# FT601.net
KiCad netlist of a schematic drawn in Altium Designer
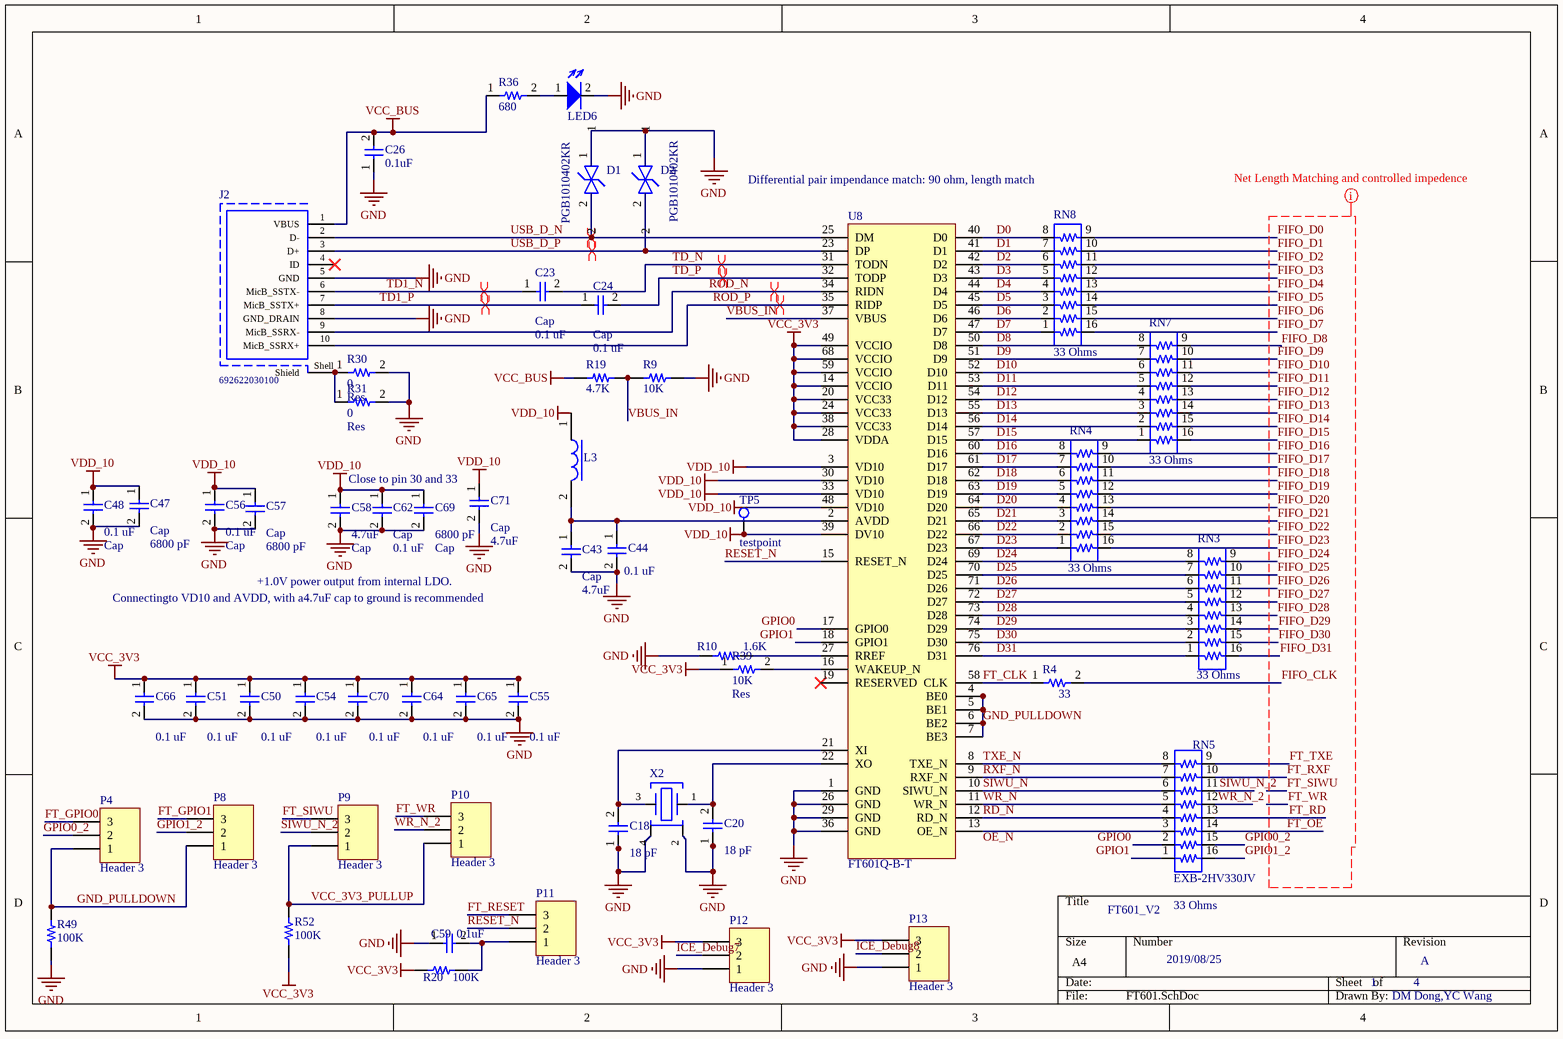
[diagram p0: FT601.SchDoc]

(export (version "E")
  (design (tool "Eeschema 10.0.6"))
  (components
    (comp (ref "C18")
      (value "18 pF")
      (footprint "CAP_18pF_0603")
      (description "Multilayer Ceramic Capacitors MLCC - SMD/SMT 50V 18pF 0603 X7R 10% AEC-Q200")
      (fields (field (name "Comment") "C0603C180K5RACAUTO"))
      (libsource (lib "USB_FPGA_SLM_v1") (part "Cap_18pF_0603"))
    )
    (comp (ref "C20")
      (value "18 pF")
      (footprint "CAP_18pF_0603")
      (description "Multilayer Ceramic Capacitors MLCC - SMD/SMT 50V 18pF 0603 X7R 10% AEC-Q200")
      (fields (field (name "Comment") "C0603C180K5RACAUTO"))
      (libsource (lib "USB_FPGA_SLM_v1") (part "Cap_18pF_0603"))
    )
    (comp (ref "C23")
      (value "0.1 uF")
      (footprint "Cap_0.1uF_0402")
      (description "Multilayer Ceramic Capacitors MLCC - SMD/SMT 100nF 10V X5R 10%")
      (fields
        (field (name "COMPONENT NAME") "Cap")
        (field (name "Comment") "CC0402KPX5R6BB104")
        (field (name "CREATED BY") "Daoming Dong")
      )
      (libsource (lib "USB_FPGA_SLM_v1") (part "CAP_0.1uF_0402"))
    )
    (comp (ref "C24")
      (value "0.1 uF")
      (footprint "Cap_0.1uF_0402")
      (description "Multilayer Ceramic Capacitors MLCC - SMD/SMT 100nF 10V X5R 10%")
      (fields
        (field (name "COMPONENT NAME") "Cap")
        (field (name "Comment") "CC0402KPX5R6BB104")
        (field (name "CREATED BY") "Daoming Dong")
      )
      (libsource (lib "USB_FPGA_SLM_v1") (part "CAP_0.1uF_0402"))
    )
    (comp (ref "C26")
      (value "0.1uF")
      (footprint "Cap_0.1uF")
      (description "Multilayer Ceramic Capacitors MLCC - SMD/SMT 0.1uF 10% 50V AEC-Q200")
      (fields (field (name "Comment") "AC0603KRX7R9BB104") (field (name "CREATED BY") "Daoming Dong"))
      (libsource (lib "USB_FPGA_SLM_v1") (part "Cap_0.1uF"))
    )
    (comp (ref "C43")
      (value "4.7uF")
      (footprint "CAP_4.7uF_0402")
      (description "Multilayer Ceramic Capacitors MLCC - SMD/SMT 0402 6.3V 4.7uF X5R 10% T: 0.5mm")
      (fields
        (field (name "COMPONENT NAME") "Cap")
        (field (name "Comment") "C1005X5R0J475K050BC")
        (field (name "CREATED BY") "Daoming Dong")
      )
      (libsource (lib "USB_FPGA_SLM_v1") (part "Cap_4.7uF_0402"))
    )
    (comp (ref "C44")
      (value "0.1 uF")
      (footprint "Cap_0.1uF_0402")
      (description "Multilayer Ceramic Capacitors MLCC - SMD/SMT 100nF 10V X5R 10%")
      (fields (field (name "Comment") "CC0402KPX5R6BB104") (field (name "CREATED BY") "Daoming Dong"))
      (libsource (lib "USB_FPGA_SLM_v1") (part "CAP_0.1uF_0402"))
    )
    (comp (ref "C47")
      (value "6800 pF")
      (footprint "CAP_6700pF_0402")
      (description "Multilayer Ceramic Capacitors MLCC - SMD/SMT 50V 6800pF X7R 0402 10% AEC-Q200")
      (fields
        (field (name "COMPONENT NAME") "Cap")
        (field (name "Comment") "C0402C682K5RECAUTO")
        (field (name "CREATED BY") "Daoming Dong")
      )
      (libsource (lib "USB_FPGA_SLM_v1") (part "Cap_6800pF_0402"))
    )
    (comp (ref "C48")
      (value "0.1 uF")
      (footprint "Cap_0.1uF_0402")
      (description "Multilayer Ceramic Capacitors MLCC - SMD/SMT 100nF 10V X5R 10%")
      (fields
        (field (name "COMPONENT NAME") "Cap")
        (field (name "Comment") "CC0402KPX5R6BB104")
        (field (name "CREATED BY") "Daoming Dong")
      )
      (libsource (lib "USB_FPGA_SLM_v1") (part "CAP_0.1uF_0402"))
    )
    (comp (ref "C50")
      (value "0.1 uF")
      (footprint "Cap_0.1uF_0402")
      (description "Multilayer Ceramic Capacitors MLCC - SMD/SMT 100nF 10V X5R 10%")
      (fields (field (name "Comment") "CC0402KPX5R6BB104") (field (name "CREATED BY") "Daoming Dong"))
      (libsource (lib "USB_FPGA_SLM_v1") (part "CAP_0.1uF_0402"))
    )
    (comp (ref "C51")
      (value "0.1 uF")
      (footprint "Cap_0.1uF_0402")
      (description "Multilayer Ceramic Capacitors MLCC - SMD/SMT 100nF 10V X5R 10%")
      (fields (field (name "Comment") "CC0402KPX5R6BB104") (field (name "CREATED BY") "Daoming Dong"))
      (libsource (lib "USB_FPGA_SLM_v1") (part "CAP_0.1uF_0402"))
    )
    (comp (ref "C54")
      (value "0.1 uF")
      (footprint "Cap_0.1uF_0402")
      (description "Multilayer Ceramic Capacitors MLCC - SMD/SMT 100nF 10V X5R 10%")
      (fields (field (name "Comment") "CC0402KPX5R6BB104") (field (name "CREATED BY") "Daoming Dong"))
      (libsource (lib "USB_FPGA_SLM_v1") (part "CAP_0.1uF_0402"))
    )
    (comp (ref "C55")
      (value "0.1 uF")
      (footprint "Cap_0.1uF_0402")
      (description "Multilayer Ceramic Capacitors MLCC - SMD/SMT 100nF 10V X5R 10%")
      (fields (field (name "Comment") "CC0402KPX5R6BB104") (field (name "CREATED BY") "Daoming Dong"))
      (libsource (lib "USB_FPGA_SLM_v1") (part "CAP_0.1uF_0402"))
    )
    (comp (ref "C56")
      (value "0.1 uF")
      (footprint "Cap_0.1uF_0402")
      (description "Multilayer Ceramic Capacitors MLCC - SMD/SMT 100nF 10V X5R 10%")
      (fields
        (field (name "COMPONENT NAME") "Cap")
        (field (name "Comment") "CC0402KPX5R6BB104")
        (field (name "CREATED BY") "Daoming Dong")
      )
      (libsource (lib "USB_FPGA_SLM_v1") (part "CAP_0.1uF_0402"))
    )
    (comp (ref "C57")
      (value "6800 pF")
      (footprint "CAP_6700pF_0402")
      (description "Multilayer Ceramic Capacitors MLCC - SMD/SMT 50V 6800pF X7R 0402 10% AEC-Q200")
      (fields
        (field (name "COMPONENT NAME") "Cap")
        (field (name "Comment") "C0402C682K5RECAUTO")
        (field (name "CREATED BY") "Daoming Dong")
      )
      (libsource (lib "USB_FPGA_SLM_v1") (part "Cap_6800pF_0402"))
    )
    (comp (ref "C58")
      (value "4.7uF")
      (footprint "CAP_4.7uF_0402")
      (description "Multilayer Ceramic Capacitors MLCC - SMD/SMT 0402 6.3V 4.7uF X5R 10% T: 0.5mm")
      (fields
        (field (name "COMPONENT NAME") "Cap")
        (field (name "Comment") "C1005X5R0J475K050BC")
        (field (name "CREATED BY") "Daoming Dong")
      )
      (libsource (lib "USB_FPGA_SLM_v1") (part "Cap_4.7uF_0402"))
    )
    (comp (ref "C59")
      (value "0.1uF")
      (footprint "Cap_0.1uF")
      (description "Multilayer Ceramic Capacitors MLCC - SMD/SMT 0.1uF 10% 50V AEC-Q200")
      (fields (field (name "Comment") "AC0603KRX7R9BB104") (field (name "CREATED BY") "Daoming Dong"))
      (libsource (lib "USB_FPGA_SLM_v1") (part "Cap_0.1uF"))
    )
    (comp (ref "C62")
      (value "0.1 uF")
      (footprint "Cap_0.1uF_0402")
      (description "Multilayer Ceramic Capacitors MLCC - SMD/SMT 100nF 10V X5R 10%")
      (fields
        (field (name "COMPONENT NAME") "Cap")
        (field (name "Comment") "CC0402KPX5R6BB104")
        (field (name "CREATED BY") "Daoming Dong")
      )
      (libsource (lib "USB_FPGA_SLM_v1") (part "CAP_0.1uF_0402"))
    )
    (comp (ref "C64")
      (value "0.1 uF")
      (footprint "Cap_0.1uF_0402")
      (description "Multilayer Ceramic Capacitors MLCC - SMD/SMT 100nF 10V X5R 10%")
      (fields (field (name "Comment") "CC0402KPX5R6BB104") (field (name "CREATED BY") "Daoming Dong"))
      (libsource (lib "USB_FPGA_SLM_v1") (part "CAP_0.1uF_0402"))
    )
    (comp (ref "C65")
      (value "0.1 uF")
      (footprint "Cap_0.1uF_0402")
      (description "Multilayer Ceramic Capacitors MLCC - SMD/SMT 100nF 10V X5R 10%")
      (fields (field (name "Comment") "CC0402KPX5R6BB104") (field (name "CREATED BY") "Daoming Dong"))
      (libsource (lib "USB_FPGA_SLM_v1") (part "CAP_0.1uF_0402"))
    )
    (comp (ref "C66")
      (value "0.1 uF")
      (footprint "Cap_0.1uF_0402")
      (description "Multilayer Ceramic Capacitors MLCC - SMD/SMT 100nF 10V X5R 10%")
      (fields (field (name "Comment") "CC0402KPX5R6BB104") (field (name "CREATED BY") "Daoming Dong"))
      (libsource (lib "USB_FPGA_SLM_v1") (part "CAP_0.1uF_0402"))
    )
    (comp (ref "C69")
      (value "6800 pF")
      (footprint "CAP_6700pF_0402")
      (description "Multilayer Ceramic Capacitors MLCC - SMD/SMT 50V 6800pF X7R 0402 10% AEC-Q200")
      (fields
        (field (name "COMPONENT NAME") "Cap")
        (field (name "Comment") "C0402C682K5RECAUTO")
        (field (name "CREATED BY") "Daoming Dong")
      )
      (libsource (lib "USB_FPGA_SLM_v1") (part "Cap_6800pF_0402"))
    )
    (comp (ref "C70")
      (value "0.1 uF")
      (footprint "Cap_0.1uF_0402")
      (description "Multilayer Ceramic Capacitors MLCC - SMD/SMT 100nF 10V X5R 10%")
      (fields (field (name "Comment") "CC0402KPX5R6BB104") (field (name "CREATED BY") "Daoming Dong"))
      (libsource (lib "USB_FPGA_SLM_v1") (part "CAP_0.1uF_0402"))
    )
    (comp (ref "C71")
      (value "4.7uF")
      (footprint "CAP_4.7uF_0402")
      (description "Multilayer Ceramic Capacitors MLCC - SMD/SMT 0402 6.3V 4.7uF X5R 10% T: 0.5mm")
      (fields
        (field (name "COMPONENT NAME") "Cap")
        (field (name "Comment") "C1005X5R0J475K050BC")
        (field (name "CREATED BY") "Daoming Dong")
      )
      (libsource (lib "USB_FPGA_SLM_v1") (part "Cap_4.7uF_0402"))
    )
    (comp (ref "D1")
      (value "PGB1010402KR")
      (footprint "ESD_Suppressor")
      (description "ESD Suppressors / TVS Diodes PULSEGUARD 0402 ESD SUPPRESSOR")
      (fields (field (name "CREATED BY") "Daoming Dong"))
      (libsource (lib "USB_FPGA_SLM_v1") (part "ESD_Suppresor"))
    )
    (comp (ref "D2")
      (value "PGB1010402KR")
      (footprint "ESD_Suppressor")
      (description "ESD Suppressors / TVS Diodes PULSEGUARD 0402 ESD SUPPRESSOR")
      (fields (field (name "CREATED BY") "Daoming Dong"))
      (libsource (lib "USB_FPGA_SLM_v1") (part "ESD_Suppresor"))
    )
    (comp (ref "J2")
      (value "692622030100")
      (footprint "692622030100")
      (description "Micro USB 3.0 Type B Receptacle WR-COM, Horizontal, SMT, with Pads")
      (fields (field (name "PUBLISHER") "Wurth Elektronik"))
      (libsource (lib "Altium_WR-COM_USB-Connectors (rev18d)") (part "692622030100"))
    )
    (comp (ref "L3")
      (value "BLM18PG300SZ1D")
      (footprint "FerriteBeads")
      (description "Ferrite Beads 0603 30ohms 1000mA Auto Infotainment")
      (fields (field (name "CREATED BY") "Daoming Dong"))
      (libsource (lib "USB_FPGA_SLM_v1") (part "FerriteBeadForFT601"))
    )
    (comp (ref "LED6")
      (value "TLMS1000-GS08")
      (footprint "LED_RED")
      (description "Standard LEDs - SMD RED")
      (fields (field (name "CREATED BY") "Daoming Dong"))
      (libsource (lib "USB_FPGA_SLM_v1") (part "LED_RED"))
    )
    (comp (ref "P4")
      (value "Header 3")
      (footprint "HDR1X3")
      (description "Header, 3-Pin")
      (fields (field (name "PUBLISHER") "Altium Limited"))
      (libsource (lib "Miscellaneous Connectors") (part "Header 3"))
    )
    (comp (ref "P8")
      (value "Header 3")
      (footprint "HDR1X3")
      (description "Header, 3-Pin")
      (fields (field (name "PUBLISHER") "Altium Limited"))
      (libsource (lib "Miscellaneous Connectors") (part "Header 3"))
    )
    (comp (ref "P9")
      (value "Header 3")
      (footprint "HDR1X3")
      (description "Header, 3-Pin")
      (fields (field (name "PUBLISHER") "Altium Limited"))
      (libsource (lib "Miscellaneous Connectors") (part "Header 3"))
    )
    (comp (ref "P10")
      (value "Header 3")
      (footprint "HDR1X3")
      (description "Header, 3-Pin")
      (fields (field (name "PUBLISHER") "Altium Limited"))
      (libsource (lib "Miscellaneous Connectors") (part "Header 3"))
    )
    (comp (ref "P11")
      (value "Header 3")
      (footprint "HDR1X3")
      (description "Header, 3-Pin")
      (fields (field (name "PUBLISHER") "Altium Limited"))
      (libsource (lib "Miscellaneous Connectors") (part "Header 3"))
    )
    (comp (ref "P12")
      (value "Header 3")
      (footprint "HDR1X3")
      (description "Header, 3-Pin")
      (fields (field (name "PUBLISHER") "Altium Limited"))
      (libsource (lib "Miscellaneous Connectors") (part "Header 3"))
    )
    (comp (ref "P13")
      (value "Header 3")
      (footprint "HDR1X3")
      (description "Header, 3-Pin")
      (fields (field (name "PUBLISHER") "Altium Limited"))
      (libsource (lib "Miscellaneous Connectors") (part "Header 3"))
    )
    (comp (ref "R4")
      (value "33")
      (footprint "Res_33_0402")
      (description "Thick Film Resistors - SMD 0402 Resistor 0.5% 100ppm 33Ohm")
      (fields (field (name "Comment") "ERJ2RKD33R0X") (field (name "CREATED BY.") "Daoming Dong"))
      (libsource (lib "USB_FPGA_SLM_v1") (part "Res_33_0402"))
    )
    (comp (ref "R9")
      (value "10K")
      (footprint "RES_10K")
      (description "Thin Film Resistors - SMD 10K ohm 0.05% 50 ppm High-Precision")
      (fields (field (name "Comment") "RT0603WRE0710KL") (field (name "CREATED BY") "Daoming Dong"))
      (libsource (lib "USB_FPGA_SLM_v1") (part "Res_10K"))
    )
    (comp (ref "R10")
      (value "1.6K")
      (footprint "RES_1.6K")
      (description "Thick Film Resistors - SMD 0603 Resistor 0.5% 50ppm 1.6KOhm")
      (fields (field (name "Comment") "ERJ-3RBD1601V") (field (name "CREATED BY") "Daoming Dong"))
      (libsource (lib "USB_FPGA_SLM_v1") (part "Res_1.6K"))
    )
    (comp (ref "R19")
      (value "4.7K")
      (footprint "RES_4.7K")
      (description "Thick Film Resistors - SMD 4.7K ohm 5% 1/10W AEC-Q200")
      (fields (field (name "Comment") "AC0603JR-134K7L") (field (name "CREATED BY") "Daoming Dong"))
      (libsource (lib "USB_FPGA_SLM_v1") (part "Res_4.7K"))
    )
    (comp (ref "R20")
      (value "100K")
      (footprint "RES_100K")
      (description "Thick Film Resistors - SMD 100K ohm 10% 75V AEC-Q200")
      (fields (field (name "Comment") "SR0603KR-07100KL") (field (name "CREATED BY") "Daoming Dong"))
      (libsource (lib "USB_FPGA_SLM_v1") (part "Res_100K"))
    )
    (comp (ref "R30")
      (value "0")
      (footprint "RES_0")
      (description "Thick Film Resistors - SMD 1/10Watt 0ohms Commercial Use")
      (fields
        (field (name "COMPONENT NAME") "Res")
        (field (name "Comment") "CRCW06030000Z0EAC")
        (field (name "CREATED BY") "Daoming Dong")
      )
      (libsource (lib "USB_FPGA_SLM_v1") (part "Res_0"))
    )
    (comp (ref "R31")
      (value "0")
      (footprint "RES_0")
      (description "Thick Film Resistors - SMD 1/10Watt 0ohms Commercial Use")
      (fields
        (field (name "COMPONENT NAME") "Res")
        (field (name "Comment") "CRCW06030000Z0EAC")
        (field (name "CREATED BY") "Daoming Dong")
      )
      (libsource (lib "USB_FPGA_SLM_v1") (part "Res_0"))
    )
    (comp (ref "R36")
      (value "680")
      (footprint "RES_680")
      (description "Thin Film Resistors - SMD 680 ohm 1% 50 ppm Thin Film")
      (fields (field (name "Comment") "RT0603FRE13680RL") (field (name "CREATED BY") "Daoming Dong"))
      (libsource (lib "USB_FPGA_SLM_v1") (part "Res_680"))
    )
    (comp (ref "R39")
      (value "10K")
      (footprint "RES_10K")
      (description "Thin Film Resistors - SMD 10K ohm 0.05% 50 ppm High-Precision")
      (fields
        (field (name "COMPONENT NAME") "Res")
        (field (name "Comment") "RT0603WRE0710KL")
        (field (name "CREATED BY") "Daoming Dong")
      )
      (libsource (lib "") (part "Res_10K_1"))
    )
    (comp (ref "R49")
      (value "100K")
      (footprint "RESC1607X60N")
      (description "Thick Film Resistors - SMD 100K ohm 10% 75V AEC-Q200")
      (fields (field (name "Comment") "SR0603KR-07100KL") (field (name "CREATED BY") "Daoming Dong"))
      (libsource (lib "USB_FPGA_SLM_v1") (part "Res_100K"))
    )
    (comp (ref "R52")
      (value "100K")
      (footprint "RESC1607X60N")
      (description "Thick Film Resistors - SMD 100K ohm 10% 75V AEC-Q200")
      (fields (field (name "Comment") "SR0603KR-07100KL") (field (name "CREATED BY") "Daoming Dong"))
      (libsource (lib "USB_FPGA_SLM_v1") (part "Res_100K"))
    )
    (comp (ref "RN3")
      (value "33 Ohms")
      (footprint "ResArray_0")
      (description "Resistor Networks & Arrays 33 OHM 5%")
      (fields (field (name "Comment") "EXB-2HV330JV"))
      (libsource (lib "USB_FPGA_SLM_v1") (part "ResArray"))
    )
    (comp (ref "RN4")
      (value "33 Ohms")
      (footprint "ResArray_0")
      (description "Resistor Networks & Arrays 33 OHM 5%")
      (fields (field (name "Comment") "EXB-2HV330JV"))
      (libsource (lib "USB_FPGA_SLM_v1") (part "ResArray"))
    )
    (comp (ref "RN5")
      (value "EXB-2HV330JV")
      (footprint "ResArray_0")
      (description "Resistor Networks & Arrays 33 OHM 5%")
      (fields (field (name "ALTIUM_VALUE") "33 Ohms"))
      (libsource (lib "USB_FPGA_SLM_v1") (part "ResArray"))
    )
    (comp (ref "RN7")
      (value "33 Ohms")
      (footprint "ResArray_0")
      (description "Resistor Networks & Arrays 33 OHM 5%")
      (fields (field (name "Comment") "EXB-2HV330JV"))
      (libsource (lib "USB_FPGA_SLM_v1") (part "ResArray"))
    )
    (comp (ref "RN8")
      (value "33 Ohms")
      (footprint "ResArray_0")
      (description "Resistor Networks & Arrays 33 OHM 5%")
      (fields (field (name "Comment") "EXB-2HV330JV"))
      (libsource (lib "USB_FPGA_SLM_v1") (part "ResArray"))
    )
    (comp (ref "TP5")
      (value "testpoint")
      (footprint "testpoint")
      (description "Testpoint for testing voltage")
      (fields (field (name "CREATED BY") "Daoming Dong"))
      (libsource (lib "USB_FPGA_SLM_v1") (part "Testpoint"))
    )
    (comp (ref "U8")
      (value "FT601Q-B-T")
      (footprint "FT601_NoGND_Pad")
      (description "USB Interface IC USB 3.0 Super-Speed 32Bits Sync FIFO")
      (fields (field (name "CREATED BY") "Daoming Dong"))
      (libsource (lib "USB_FPGA_SLM_v1") (part "FT601Q-B-T"))
    )
    (comp (ref "X2")
      (value "ABM8G-30.000MHZ-18-D2Y-T")
      (footprint "30MHzOscillatorV2")
      (description "Crystals 30.000MHz 18pF 30ppm -40C +85C")
      (fields (field (name "CREATED BY") "Youchao Wang"))
      (libsource (lib "USB_FPGA_SLM_v1") (part "30MHzOscillator"))
    )
  )
  (nets
    (net (code "1") (name "/D0") (class "Default")
      (node (ref "RN8") (pin "8") (pinfunction "8_8") (pintype "passive"))
      (node (ref "U8") (pin "40") (pinfunction "D0_40") (pintype "passive"))
    )
    (net (code "2") (name "/D1") (class "Default")
      (node (ref "RN8") (pin "7") (pinfunction "7_7") (pintype "passive"))
      (node (ref "U8") (pin "41") (pinfunction "D1_41") (pintype "passive"))
    )
    (net (code "3") (name "/D2") (class "Default")
      (node (ref "RN8") (pin "6") (pinfunction "6_6") (pintype "passive"))
      (node (ref "U8") (pin "42") (pinfunction "D2_42") (pintype "passive"))
    )
    (net (code "4") (name "/D3") (class "Default")
      (node (ref "RN8") (pin "5") (pinfunction "5_5") (pintype "passive"))
      (node (ref "U8") (pin "43") (pinfunction "D3_43") (pintype "passive"))
    )
    (net (code "5") (name "/D4") (class "Default")
      (node (ref "RN8") (pin "4") (pinfunction "4_4") (pintype "passive"))
      (node (ref "U8") (pin "44") (pinfunction "D4_44") (pintype "passive"))
    )
    (net (code "6") (name "/D5") (class "Default")
      (node (ref "RN8") (pin "3") (pinfunction "3_3") (pintype "passive"))
      (node (ref "U8") (pin "45") (pinfunction "D5_45") (pintype "passive"))
    )
    (net (code "7") (name "/D6") (class "Default")
      (node (ref "RN8") (pin "2") (pinfunction "2_2") (pintype "passive"))
      (node (ref "U8") (pin "46") (pinfunction "D6_46") (pintype "passive"))
    )
    (net (code "8") (name "/D7") (class "Default")
      (node (ref "RN8") (pin "1") (pinfunction "1_1") (pintype "passive"))
      (node (ref "U8") (pin "47") (pinfunction "D7_47") (pintype "passive"))
    )
    (net (code "9") (name "/D8") (class "Default")
      (node (ref "RN7") (pin "8") (pinfunction "8_8") (pintype "passive"))
      (node (ref "U8") (pin "50") (pinfunction "D8_50") (pintype "passive"))
    )
    (net (code "10") (name "/D9") (class "Default")
      (node (ref "RN7") (pin "7") (pinfunction "7_7") (pintype "passive"))
      (node (ref "U8") (pin "51") (pinfunction "D9_51") (pintype "passive"))
    )
    (net (code "11") (name "/D10") (class "Default")
      (node (ref "RN7") (pin "6") (pinfunction "6_6") (pintype "passive"))
      (node (ref "U8") (pin "52") (pinfunction "D10_52") (pintype "passive"))
    )
    (net (code "12") (name "/D11") (class "Default")
      (node (ref "RN7") (pin "5") (pinfunction "5_5") (pintype "passive"))
      (node (ref "U8") (pin "53") (pinfunction "D11_53") (pintype "passive"))
    )
    (net (code "13") (name "/D12") (class "Default")
      (node (ref "RN7") (pin "4") (pinfunction "4_4") (pintype "passive"))
      (node (ref "U8") (pin "54") (pinfunction "D12_54") (pintype "passive"))
    )
    (net (code "14") (name "/D13") (class "Default")
      (node (ref "RN7") (pin "3") (pinfunction "3_3") (pintype "passive"))
      (node (ref "U8") (pin "55") (pinfunction "D13_55") (pintype "passive"))
    )
    (net (code "15") (name "/D14") (class "Default")
      (node (ref "RN7") (pin "2") (pinfunction "2_2") (pintype "passive"))
      (node (ref "U8") (pin "56") (pinfunction "D14_56") (pintype "passive"))
    )
    (net (code "16") (name "/D15") (class "Default")
      (node (ref "RN7") (pin "1") (pinfunction "1_1") (pintype "passive"))
      (node (ref "U8") (pin "57") (pinfunction "D15_57") (pintype "passive"))
    )
    (net (code "17") (name "/D16") (class "Default")
      (node (ref "RN4") (pin "8") (pinfunction "8_8") (pintype "passive"))
      (node (ref "U8") (pin "60") (pinfunction "D16_60") (pintype "passive"))
    )
    (net (code "18") (name "/D17") (class "Default")
      (node (ref "RN4") (pin "7") (pinfunction "7_7") (pintype "passive"))
      (node (ref "U8") (pin "61") (pinfunction "D17_61") (pintype "passive"))
    )
    (net (code "19") (name "/D18") (class "Default")
      (node (ref "RN4") (pin "6") (pinfunction "6_6") (pintype "passive"))
      (node (ref "U8") (pin "62") (pinfunction "D18_62") (pintype "passive"))
    )
    (net (code "20") (name "/D19") (class "Default")
      (node (ref "RN4") (pin "5") (pinfunction "5_5") (pintype "passive"))
      (node (ref "U8") (pin "63") (pinfunction "D19_63") (pintype "passive"))
    )
    (net (code "21") (name "/D20") (class "Default")
      (node (ref "RN4") (pin "4") (pinfunction "4_4") (pintype "passive"))
      (node (ref "U8") (pin "64") (pinfunction "D20_64") (pintype "passive"))
    )
    (net (code "22") (name "/D21") (class "Default")
      (node (ref "RN4") (pin "3") (pinfunction "3_3") (pintype "passive"))
      (node (ref "U8") (pin "65") (pinfunction "D21_65") (pintype "passive"))
    )
    (net (code "23") (name "/D22") (class "Default")
      (node (ref "RN4") (pin "2") (pinfunction "2_2") (pintype "passive"))
      (node (ref "U8") (pin "66") (pinfunction "D22_66") (pintype "passive"))
    )
    (net (code "24") (name "/D23") (class "Default")
      (node (ref "RN4") (pin "1") (pinfunction "1_1") (pintype "passive"))
      (node (ref "U8") (pin "67") (pinfunction "D23_67") (pintype "passive"))
    )
    (net (code "25") (name "/D24") (class "Default")
      (node (ref "RN3") (pin "8") (pinfunction "8_8") (pintype "passive"))
      (node (ref "U8") (pin "69") (pinfunction "D24_69") (pintype "passive"))
    )
    (net (code "26") (name "/D25") (class "Default")
      (node (ref "RN3") (pin "7") (pinfunction "7_7") (pintype "passive"))
      (node (ref "U8") (pin "70") (pinfunction "D25_70") (pintype "passive"))
    )
    (net (code "27") (name "/D26") (class "Default")
      (node (ref "RN3") (pin "6") (pinfunction "6_6") (pintype "passive"))
      (node (ref "U8") (pin "71") (pinfunction "D26_71") (pintype "passive"))
    )
    (net (code "28") (name "/D27") (class "Default")
      (node (ref "RN3") (pin "5") (pinfunction "5_5") (pintype "passive"))
      (node (ref "U8") (pin "72") (pinfunction "D27_72") (pintype "passive"))
    )
    (net (code "29") (name "/D28") (class "Default")
      (node (ref "RN3") (pin "4") (pinfunction "4_4") (pintype "passive"))
      (node (ref "U8") (pin "73") (pinfunction "D28_73") (pintype "passive"))
    )
    (net (code "30") (name "/D29") (class "Default")
      (node (ref "RN3") (pin "3") (pinfunction "3_3") (pintype "passive"))
      (node (ref "U8") (pin "74") (pinfunction "D29_74") (pintype "passive"))
    )
    (net (code "31") (name "/D30") (class "Default")
      (node (ref "RN3") (pin "2") (pinfunction "2_2") (pintype "passive"))
      (node (ref "U8") (pin "75") (pinfunction "D30_75") (pintype "passive"))
    )
    (net (code "32") (name "/D31") (class "Default")
      (node (ref "RN3") (pin "1") (pinfunction "1_1") (pintype "passive"))
      (node (ref "U8") (pin "76") (pinfunction "D31_76") (pintype "passive"))
    )
    (net (code "33") (name "/FIFO_CLK") (class "Default")
      (node (ref "R4") (pin "2") (pinfunction "2_2") (pintype "passive"))
    )
    (net (code "34") (name "/FIFO_D0") (class "Default")
      (node (ref "RN8") (pin "9") (pinfunction "9_9") (pintype "passive"))
    )
    (net (code "35") (name "/FIFO_D1") (class "Default")
      (node (ref "RN8") (pin "10") (pinfunction "10_10") (pintype "passive"))
    )
    (net (code "36") (name "/FIFO_D2") (class "Default")
      (node (ref "RN8") (pin "11") (pinfunction "11_11") (pintype "passive"))
    )
    (net (code "37") (name "/FIFO_D3") (class "Default")
      (node (ref "RN8") (pin "12") (pinfunction "12_12") (pintype "passive"))
    )
    (net (code "38") (name "/FIFO_D4") (class "Default")
      (node (ref "RN8") (pin "13") (pinfunction "13_13") (pintype "passive"))
    )
    (net (code "39") (name "/FIFO_D5") (class "Default")
      (node (ref "RN8") (pin "14") (pinfunction "14_14") (pintype "passive"))
    )
    (net (code "40") (name "/FIFO_D6") (class "Default")
      (node (ref "RN8") (pin "15") (pinfunction "15_15") (pintype "passive"))
    )
    (net (code "41") (name "/FIFO_D7") (class "Default")
      (node (ref "RN8") (pin "16") (pinfunction "16_16") (pintype "passive"))
    )
    (net (code "42") (name "/FIFO_D8") (class "Default")
      (node (ref "RN7") (pin "9") (pinfunction "9_9") (pintype "passive"))
    )
    (net (code "43") (name "/FIFO_D9") (class "Default")
      (node (ref "RN7") (pin "10") (pinfunction "10_10") (pintype "passive"))
    )
    (net (code "44") (name "/FIFO_D10") (class "Default")
      (node (ref "RN7") (pin "11") (pinfunction "11_11") (pintype "passive"))
    )
    (net (code "45") (name "/FIFO_D11") (class "Default")
      (node (ref "RN7") (pin "12") (pinfunction "12_12") (pintype "passive"))
    )
    (net (code "46") (name "/FIFO_D12") (class "Default")
      (node (ref "RN7") (pin "13") (pinfunction "13_13") (pintype "passive"))
    )
    (net (code "47") (name "/FIFO_D13") (class "Default")
      (node (ref "RN7") (pin "14") (pinfunction "14_14") (pintype "passive"))
    )
    (net (code "48") (name "/FIFO_D14") (class "Default")
      (node (ref "RN7") (pin "15") (pinfunction "15_15") (pintype "passive"))
    )
    (net (code "49") (name "/FIFO_D15") (class "Default")
      (node (ref "RN7") (pin "16") (pinfunction "16_16") (pintype "passive"))
    )
    (net (code "50") (name "/FIFO_D16") (class "Default")
      (node (ref "RN4") (pin "9") (pinfunction "9_9") (pintype "passive"))
    )
    (net (code "51") (name "/FIFO_D17") (class "Default")
      (node (ref "RN4") (pin "10") (pinfunction "10_10") (pintype "passive"))
    )
    (net (code "52") (name "/FIFO_D18") (class "Default")
      (node (ref "RN4") (pin "11") (pinfunction "11_11") (pintype "passive"))
    )
    (net (code "53") (name "/FIFO_D19") (class "Default")
      (node (ref "RN4") (pin "12") (pinfunction "12_12") (pintype "passive"))
    )
    (net (code "54") (name "/FIFO_D20") (class "Default")
      (node (ref "RN4") (pin "13") (pinfunction "13_13") (pintype "passive"))
    )
    (net (code "55") (name "/FIFO_D21") (class "Default")
      (node (ref "RN4") (pin "14") (pinfunction "14_14") (pintype "passive"))
    )
    (net (code "56") (name "/FIFO_D22") (class "Default")
      (node (ref "RN4") (pin "15") (pinfunction "15_15") (pintype "passive"))
    )
    (net (code "57") (name "/FIFO_D23") (class "Default")
      (node (ref "RN4") (pin "16") (pinfunction "16_16") (pintype "passive"))
    )
    (net (code "58") (name "/FIFO_D24") (class "Default")
      (node (ref "RN3") (pin "9") (pinfunction "9_9") (pintype "passive"))
    )
    (net (code "59") (name "/FIFO_D25") (class "Default")
      (node (ref "RN3") (pin "10") (pinfunction "10_10") (pintype "passive"))
    )
    (net (code "60") (name "/FIFO_D26") (class "Default")
      (node (ref "RN3") (pin "11") (pinfunction "11_11") (pintype "passive"))
    )
    (net (code "61") (name "/FIFO_D27") (class "Default")
      (node (ref "RN3") (pin "12") (pinfunction "12_12") (pintype "passive"))
    )
    (net (code "62") (name "/FIFO_D28") (class "Default")
      (node (ref "RN3") (pin "13") (pinfunction "13_13") (pintype "passive"))
    )
    (net (code "63") (name "/FIFO_D29") (class "Default")
      (node (ref "RN3") (pin "14") (pinfunction "14_14") (pintype "passive"))
    )
    (net (code "64") (name "/FIFO_D30") (class "Default")
      (node (ref "RN3") (pin "15") (pinfunction "15_15") (pintype "passive"))
    )
    (net (code "65") (name "/FIFO_D31") (class "Default")
      (node (ref "RN3") (pin "16") (pinfunction "16_16") (pintype "passive"))
    )
    (net (code "66") (name "/FT_CLK") (class "Default")
      (node (ref "R4") (pin "1") (pinfunction "1_1") (pintype "passive"))
      (node (ref "U8") (pin "58") (pinfunction "CLK_58") (pintype "passive"))
    )
    (net (code "67") (name "/FT_GPIO0") (class "Default")
      (node (ref "P4") (pin "3") (pinfunction "3_3") (pintype "passive"))
    )
    (net (code "68") (name "/FT_GPIO1") (class "Default")
      (node (ref "P8") (pin "3") (pinfunction "3_3") (pintype "passive"))
    )
    (net (code "69") (name "/FT_OE") (class "Default")
      (node (ref "RN5") (pin "14") (pinfunction "14_14") (pintype "passive"))
    )
    (net (code "70") (name "/FT_RD") (class "Default")
      (node (ref "RN5") (pin "13") (pinfunction "13_13") (pintype "passive"))
    )
    (net (code "71") (name "/FT_RESET") (class "Default")
      (node (ref "P11") (pin "3") (pinfunction "3_3") (pintype "passive"))
    )
    (net (code "72") (name "/FT_RXF") (class "Default")
      (node (ref "RN5") (pin "10") (pinfunction "10_10") (pintype "passive"))
    )
    (net (code "73") (name "/FT_SIWU") (class "Default")
      (node (ref "P9") (pin "3") (pinfunction "3_3") (pintype "passive"))
    )
    (net (code "74") (name "/FT_TXE") (class "Default")
      (node (ref "RN5") (pin "9") (pinfunction "9_9") (pintype "passive"))
    )
    (net (code "75") (name "/FT_WR") (class "Default")
      (node (ref "P10") (pin "3") (pinfunction "3_3") (pintype "passive"))
    )
    (net (code "76") (name "/GND_PULLDOWN") (class "Default")
      (node (ref "P4") (pin "1") (pinfunction "1_1") (pintype "passive"))
      (node (ref "P8") (pin "1") (pinfunction "1_1") (pintype "passive"))
      (node (ref "R49") (pin "2") (pinfunction "2_2") (pintype "passive"))
      (node (ref "U8") (pin "4") (pinfunction "BE0_4") (pintype "passive"))
      (node (ref "U8") (pin "5") (pinfunction "BE1_5") (pintype "passive"))
      (node (ref "U8") (pin "6") (pinfunction "BE2_6") (pintype "passive"))
      (node (ref "U8") (pin "7") (pinfunction "BE3_7") (pintype "passive"))
    )
    (net (code "77") (name "/GPIO0") (class "Default")
      (node (ref "RN5") (pin "2") (pinfunction "2_2") (pintype "passive"))
      (node (ref "U8") (pin "17") (pinfunction "GPIO0_17") (pintype "passive"))
    )
    (net (code "78") (name "/GPIO0_2") (class "Default")
      (node (ref "P4") (pin "2") (pinfunction "2_2") (pintype "passive"))
      (node (ref "RN5") (pin "15") (pinfunction "15_15") (pintype "passive"))
    )
    (net (code "79") (name "/GPIO1") (class "Default")
      (node (ref "RN5") (pin "1") (pinfunction "1_1") (pintype "passive"))
      (node (ref "U8") (pin "18") (pinfunction "GPIO1_18") (pintype "passive"))
    )
    (net (code "80") (name "/GPIO1_2") (class "Default")
      (node (ref "P8") (pin "2") (pinfunction "2_2") (pintype "passive"))
      (node (ref "RN5") (pin "16") (pinfunction "16_16") (pintype "passive"))
    )
    (net (code "81") (name "/ICE_Debug7") (class "Default")
      (node (ref "P12") (pin "2") (pinfunction "2_2") (pintype "passive"))
    )
    (net (code "82") (name "/ICE_Debug8") (class "Default")
      (node (ref "P13") (pin "2") (pinfunction "2_2") (pintype "passive"))
    )
    (net (code "84") (name "/RD_N") (class "Default")
      (node (ref "RN5") (pin "4") (pinfunction "4_4") (pintype "passive"))
      (node (ref "U8") (pin "12") (pinfunction "RD_N_12") (pintype "passive"))
    )
    (net (code "85") (name "/RESET_N") (class "Default")
      (node (ref "P11") (pin "2") (pinfunction "2_2") (pintype "passive"))
      (node (ref "U8") (pin "15") (pinfunction "RESET_N_15") (pintype "passive"))
    )
    (net (code "86") (name "/ROD_N") (class "Default")
      (node (ref "J2") (pin "9") (pinfunction "MicB_SSRX-_9") (pintype "passive"))
      (node (ref "U8") (pin "34") (pinfunction "RIDN_34") (pintype "passive"))
    )
    (net (code "87") (name "/ROD_P") (class "Default")
      (node (ref "J2") (pin "10") (pinfunction "MicB_SSRX+_10") (pintype "passive"))
      (node (ref "U8") (pin "35") (pinfunction "RIDP_35") (pintype "passive"))
    )
    (net (code "88") (name "/RXF_N") (class "Default")
      (node (ref "RN5") (pin "7") (pinfunction "7_7") (pintype "passive"))
      (node (ref "U8") (pin "9") (pinfunction "RXF_N_9") (pintype "passive"))
    )
    (net (code "89") (name "/SIWU_N") (class "Default")
      (node (ref "RN5") (pin "6") (pinfunction "6_6") (pintype "passive"))
      (node (ref "U8") (pin "10") (pinfunction "SIWU_N_10") (pintype "passive"))
    )
    (net (code "90") (name "/SIWU_N_2") (class "Default")
      (node (ref "P9") (pin "2") (pinfunction "2_2") (pintype "passive"))
      (node (ref "RN5") (pin "11") (pinfunction "11_11") (pintype "passive"))
    )
    (net (code "91") (name "/TD1_N") (class "Default")
      (node (ref "C23") (pin "1") (pinfunction "1_1") (pintype "passive"))
      (node (ref "J2") (pin "6") (pinfunction "MicB_SSTX-_6") (pintype "passive"))
    )
    (net (code "92") (name "/TD1_P") (class "Default")
      (node (ref "C24") (pin "1") (pinfunction "1_1") (pintype "passive"))
      (node (ref "J2") (pin "7") (pinfunction "MicB_SSTX+_7") (pintype "passive"))
    )
    (net (code "93") (name "/TD_N") (class "Default")
      (node (ref "C23") (pin "2") (pinfunction "2_2") (pintype "passive"))
      (node (ref "U8") (pin "31") (pinfunction "TODN_31") (pintype "passive"))
    )
    (net (code "94") (name "/TD_P") (class "Default")
      (node (ref "C24") (pin "2") (pinfunction "2_2") (pintype "passive"))
      (node (ref "U8") (pin "32") (pinfunction "TODP_32") (pintype "passive"))
    )
    (net (code "95") (name "/TXE_N") (class "Default")
      (node (ref "RN5") (pin "8") (pinfunction "8_8") (pintype "passive"))
      (node (ref "U8") (pin "8") (pinfunction "TXE_N_8") (pintype "passive"))
    )
    (net (code "96") (name "/USB_D_N") (class "Default")
      (node (ref "D1") (pin "2") (pinfunction "2_2") (pintype "passive"))
      (node (ref "J2") (pin "2") (pinfunction "D-_2") (pintype "passive"))
      (node (ref "U8") (pin "25") (pinfunction "DM_25") (pintype "passive"))
    )
    (net (code "97") (name "/USB_D_P") (class "Default")
      (node (ref "D2") (pin "2") (pinfunction "2_2") (pintype "passive"))
      (node (ref "J2") (pin "3") (pinfunction "D+_3") (pintype "passive"))
      (node (ref "U8") (pin "23") (pinfunction "DP_23") (pintype "passive"))
    )
    (net (code "98") (name "/VBUS_IN") (class "Default")
      (node (ref "R19") (pin "1") (pinfunction "1_1") (pintype "passive"))
      (node (ref "R9") (pin "2") (pinfunction "2_2") (pintype "passive"))
      (node (ref "U8") (pin "37") (pinfunction "VBUS_37") (pintype "passive"))
    )
    (net (code "99") (name "/VCC_3V3_PULLUP") (class "Default")
      (node (ref "P10") (pin "1") (pinfunction "1_1") (pintype "passive"))
      (node (ref "P9") (pin "1") (pinfunction "1_1") (pintype "passive"))
      (node (ref "R52") (pin "2") (pinfunction "2_2") (pintype "passive"))
    )
    (net (code "100") (name "/WR_N") (class "Default")
      (node (ref "RN5") (pin "5") (pinfunction "5_5") (pintype "passive"))
      (node (ref "U8") (pin "11") (pinfunction "WR_N_11") (pintype "passive"))
    )
    (net (code "101") (name "/WR_N_2") (class "Default")
      (node (ref "P10") (pin "2") (pinfunction "2_2") (pintype "passive"))
      (node (ref "RN5") (pin "12") (pinfunction "12_12") (pintype "passive"))
    )
    (net (code "102") (name "GND") (class "Default")
      (node (ref "C18") (pin "1") (pinfunction "1_1") (pintype "passive"))
      (node (ref "C20") (pin "1") (pinfunction "1_1") (pintype "passive"))
      (node (ref "C26") (pin "1") (pinfunction "1_1") (pintype "passive"))
      (node (ref "C43") (pin "2") (pinfunction "2_2") (pintype "passive"))
      (node (ref "C44") (pin "2") (pinfunction "2_2") (pintype "passive"))
      (node (ref "C47") (pin "2") (pinfunction "2_2") (pintype "passive"))
      (node (ref "C48") (pin "2") (pinfunction "2_2") (pintype "passive"))
      (node (ref "C50") (pin "2") (pinfunction "2_2") (pintype "passive"))
      (node (ref "C51") (pin "2") (pinfunction "2_2") (pintype "passive"))
      (node (ref "C54") (pin "2") (pinfunction "2_2") (pintype "passive"))
      (node (ref "C55") (pin "2") (pinfunction "2_2") (pintype "passive"))
      (node (ref "C56") (pin "2") (pinfunction "2_2") (pintype "passive"))
      (node (ref "C57") (pin "2") (pinfunction "2_2") (pintype "passive"))
      (node (ref "C58") (pin "2") (pinfunction "2_2") (pintype "passive"))
      (node (ref "C59") (pin "1") (pinfunction "1_1") (pintype "passive"))
      (node (ref "C62") (pin "2") (pinfunction "2_2") (pintype "passive"))
      (node (ref "C64") (pin "2") (pinfunction "2_2") (pintype "passive"))
      (node (ref "C65") (pin "2") (pinfunction "2_2") (pintype "passive"))
      (node (ref "C66") (pin "2") (pinfunction "2_2") (pintype "passive"))
      (node (ref "C69") (pin "2") (pinfunction "2_2") (pintype "passive"))
      (node (ref "C70") (pin "2") (pinfunction "2_2") (pintype "passive"))
      (node (ref "C71") (pin "2") (pinfunction "2_2") (pintype "passive"))
      (node (ref "D1") (pin "1") (pinfunction "1_1") (pintype "passive"))
      (node (ref "D2") (pin "1") (pinfunction "1_1") (pintype "passive"))
      (node (ref "J2") (pin "5") (pinfunction "GND_5") (pintype "passive"))
      (node (ref "J2") (pin "8") (pinfunction "GND_DRAIN_8") (pintype "passive"))
      (node (ref "LED6") (pin "2") (pinfunction "Cathode_2") (pintype "passive"))
      (node (ref "P12") (pin "1") (pinfunction "1_1") (pintype "passive"))
      (node (ref "P13") (pin "1") (pinfunction "1_1") (pintype "passive"))
      (node (ref "R10") (pin "1") (pinfunction "1_1") (pintype "passive"))
      (node (ref "R30") (pin "2") (pinfunction "2_2") (pintype "passive"))
      (node (ref "R31") (pin "2") (pinfunction "2_2") (pintype "passive"))
      (node (ref "R49") (pin "1") (pinfunction "1_1") (pintype "passive"))
      (node (ref "R9") (pin "1") (pinfunction "1_1") (pintype "passive"))
      (node (ref "U8") (pin "1") (pinfunction "GND_1") (pintype "passive"))
      (node (ref "U8") (pin "26") (pinfunction "GND_26") (pintype "passive"))
      (node (ref "U8") (pin "29") (pinfunction "GND_29") (pintype "passive"))
      (node (ref "U8") (pin "36") (pinfunction "GND_36") (pintype "passive"))
      (node (ref "X2") (pin "2") (pinfunction "GND_2") (pintype "passive"))
      (node (ref "X2") (pin "4") (pinfunction "GND_4") (pintype "passive"))
    )
    (net (code "103") (name "Net-(C59-Pad2)") (class "Default")
      (node (ref "C59") (pin "2") (pinfunction "2_2") (pintype "passive"))
      (node (ref "P11") (pin "1") (pinfunction "1_1") (pintype "passive"))
      (node (ref "R20") (pin "2") (pinfunction "2_2") (pintype "passive"))
    )
    (net (code "104") (name "Net-(J2-Shield)") (class "Default")
      (node (ref "J2") (pin "Shell") (pinfunction "Shield_Shell") (pintype "passive"))
      (node (ref "R30") (pin "1") (pinfunction "1_1") (pintype "passive"))
      (node (ref "R31") (pin "1") (pinfunction "1_1") (pintype "passive"))
    )
    (net (code "105") (name "Net-(LED6-Anode)") (class "Default")
      (node (ref "LED6") (pin "1") (pinfunction "Anode_1") (pintype "passive"))
      (node (ref "R36") (pin "2") (pinfunction "2_2") (pintype "passive"))
    )
    (net (code "106") (name "Net-(U8-AVDD)") (class "Default")
      (node (ref "C43") (pin "1") (pinfunction "1_1") (pintype "passive"))
      (node (ref "C44") (pin "1") (pinfunction "1_1") (pintype "passive"))
      (node (ref "L3") (pin "2") (pinfunction "2_2") (pintype "passive"))
      (node (ref "U8") (pin "2") (pinfunction "AVDD_2") (pintype "passive"))
    )
    (net (code "107") (name "Net-(U8-OE_N)") (class "Default")
      (node (ref "RN5") (pin "3") (pinfunction "3_3") (pintype "passive"))
      (node (ref "U8") (pin "13") (pinfunction "OE_N_13") (pintype "passive"))
    )
    (net (code "108") (name "Net-(U8-RREF)") (class "Default")
      (node (ref "R10") (pin "2") (pinfunction "2_2") (pintype "passive"))
      (node (ref "U8") (pin "27") (pinfunction "RREF_27") (pintype "passive"))
    )
    (net (code "109") (name "Net-(U8-WAKEUP_N)") (class "Default")
      (node (ref "R39") (pin "2") (pinfunction "2_2") (pintype "passive"))
      (node (ref "U8") (pin "16") (pinfunction "WAKEUP_N_16") (pintype "passive"))
    )
    (net (code "110") (name "Net-(U8-XI)") (class "Default")
      (node (ref "C18") (pin "2") (pinfunction "2_2") (pintype "passive"))
      (node (ref "U8") (pin "21") (pinfunction "XI_21") (pintype "passive"))
      (node (ref "X2") (pin "3") (pinfunction "HOT_3") (pintype "passive"))
    )
    (net (code "111") (name "Net-(U8-XO)") (class "Default")
      (node (ref "C20") (pin "2") (pinfunction "2_2") (pintype "passive"))
      (node (ref "U8") (pin "22") (pinfunction "XO_22") (pintype "passive"))
      (node (ref "X2") (pin "1") (pinfunction "HOT_1") (pintype "passive"))
    )
    (net (code "112") (name "VCC_3V3") (class "Default")
      (node (ref "C50") (pin "1") (pinfunction "1_1") (pintype "passive"))
      (node (ref "C51") (pin "1") (pinfunction "1_1") (pintype "passive"))
      (node (ref "C54") (pin "1") (pinfunction "1_1") (pintype "passive"))
      (node (ref "C55") (pin "1") (pinfunction "1_1") (pintype "passive"))
      (node (ref "C64") (pin "1") (pinfunction "1_1") (pintype "passive"))
      (node (ref "C65") (pin "1") (pinfunction "1_1") (pintype "passive"))
      (node (ref "C66") (pin "1") (pinfunction "1_1") (pintype "passive"))
      (node (ref "C70") (pin "1") (pinfunction "1_1") (pintype "passive"))
      (node (ref "P12") (pin "3") (pinfunction "3_3") (pintype "passive"))
      (node (ref "P13") (pin "3") (pinfunction "3_3") (pintype "passive"))
      (node (ref "R20") (pin "1") (pinfunction "1_1") (pintype "passive"))
      (node (ref "R39") (pin "1") (pinfunction "1_1") (pintype "passive"))
      (node (ref "R52") (pin "1") (pinfunction "1_1") (pintype "passive"))
      (node (ref "U8") (pin "14") (pinfunction "VCCIO_14") (pintype "passive"))
      (node (ref "U8") (pin "20") (pinfunction "VCC33_20") (pintype "passive"))
      (node (ref "U8") (pin "24") (pinfunction "VCC33_24") (pintype "passive"))
      (node (ref "U8") (pin "28") (pinfunction "VDDA_28") (pintype "passive"))
      (node (ref "U8") (pin "38") (pinfunction "VCC33_38") (pintype "passive"))
      (node (ref "U8") (pin "49") (pinfunction "VCCIO_49") (pintype "passive"))
      (node (ref "U8") (pin "59") (pinfunction "VCCIO_59") (pintype "passive"))
      (node (ref "U8") (pin "68") (pinfunction "VCCIO_68") (pintype "passive"))
    )
    (net (code "113") (name "VCC_BUS") (class "Default")
      (node (ref "C26") (pin "2") (pinfunction "2_2") (pintype "passive"))
      (node (ref "J2") (pin "1") (pinfunction "VBUS_1") (pintype "passive"))
      (node (ref "R19") (pin "2") (pinfunction "2_2") (pintype "passive"))
      (node (ref "R36") (pin "1") (pinfunction "1_1") (pintype "passive"))
    )
    (net (code "114") (name "VDD_10") (class "Default")
      (node (ref "C47") (pin "1") (pinfunction "1_1") (pintype "passive"))
      (node (ref "C48") (pin "1") (pinfunction "1_1") (pintype "passive"))
      (node (ref "C56") (pin "1") (pinfunction "1_1") (pintype "passive"))
      (node (ref "C57") (pin "1") (pinfunction "1_1") (pintype "passive"))
      (node (ref "C58") (pin "1") (pinfunction "1_1") (pintype "passive"))
      (node (ref "C62") (pin "1") (pinfunction "1_1") (pintype "passive"))
      (node (ref "C69") (pin "1") (pinfunction "1_1") (pintype "passive"))
      (node (ref "C71") (pin "1") (pinfunction "1_1") (pintype "passive"))
      (node (ref "L3") (pin "1") (pinfunction "1_1") (pintype "passive"))
      (node (ref "TP5") (pin "1") (pinfunction "1_1") (pintype "passive"))
      (node (ref "U8") (pin "3") (pinfunction "VD10_3") (pintype "passive"))
      (node (ref "U8") (pin "30") (pinfunction "VD10_30") (pintype "passive"))
      (node (ref "U8") (pin "33") (pinfunction "VD10_33") (pintype "passive"))
      (node (ref "U8") (pin "39") (pinfunction "DV10_39") (pintype "passive"))
      (node (ref "U8") (pin "48") (pinfunction "VD10_48") (pintype "passive"))
    )
    (net (code "115") (name "unconnected-(J2-ID-Pad4)") (class "Default")
      (node (ref "J2") (pin "4") (pinfunction "ID_4") (pintype "passive+no_connect"))
    )
    (net (code "116") (name "unconnected-(U8-RESERVED-Pad19)") (class "Default")
      (node (ref "U8") (pin "19") (pinfunction "RESERVED_19") (pintype "passive+no_connect"))
    )
  )
)
